# schematic_motor_driver_v3.net
KiCad netlist of a schematic drawn in Altium Designer
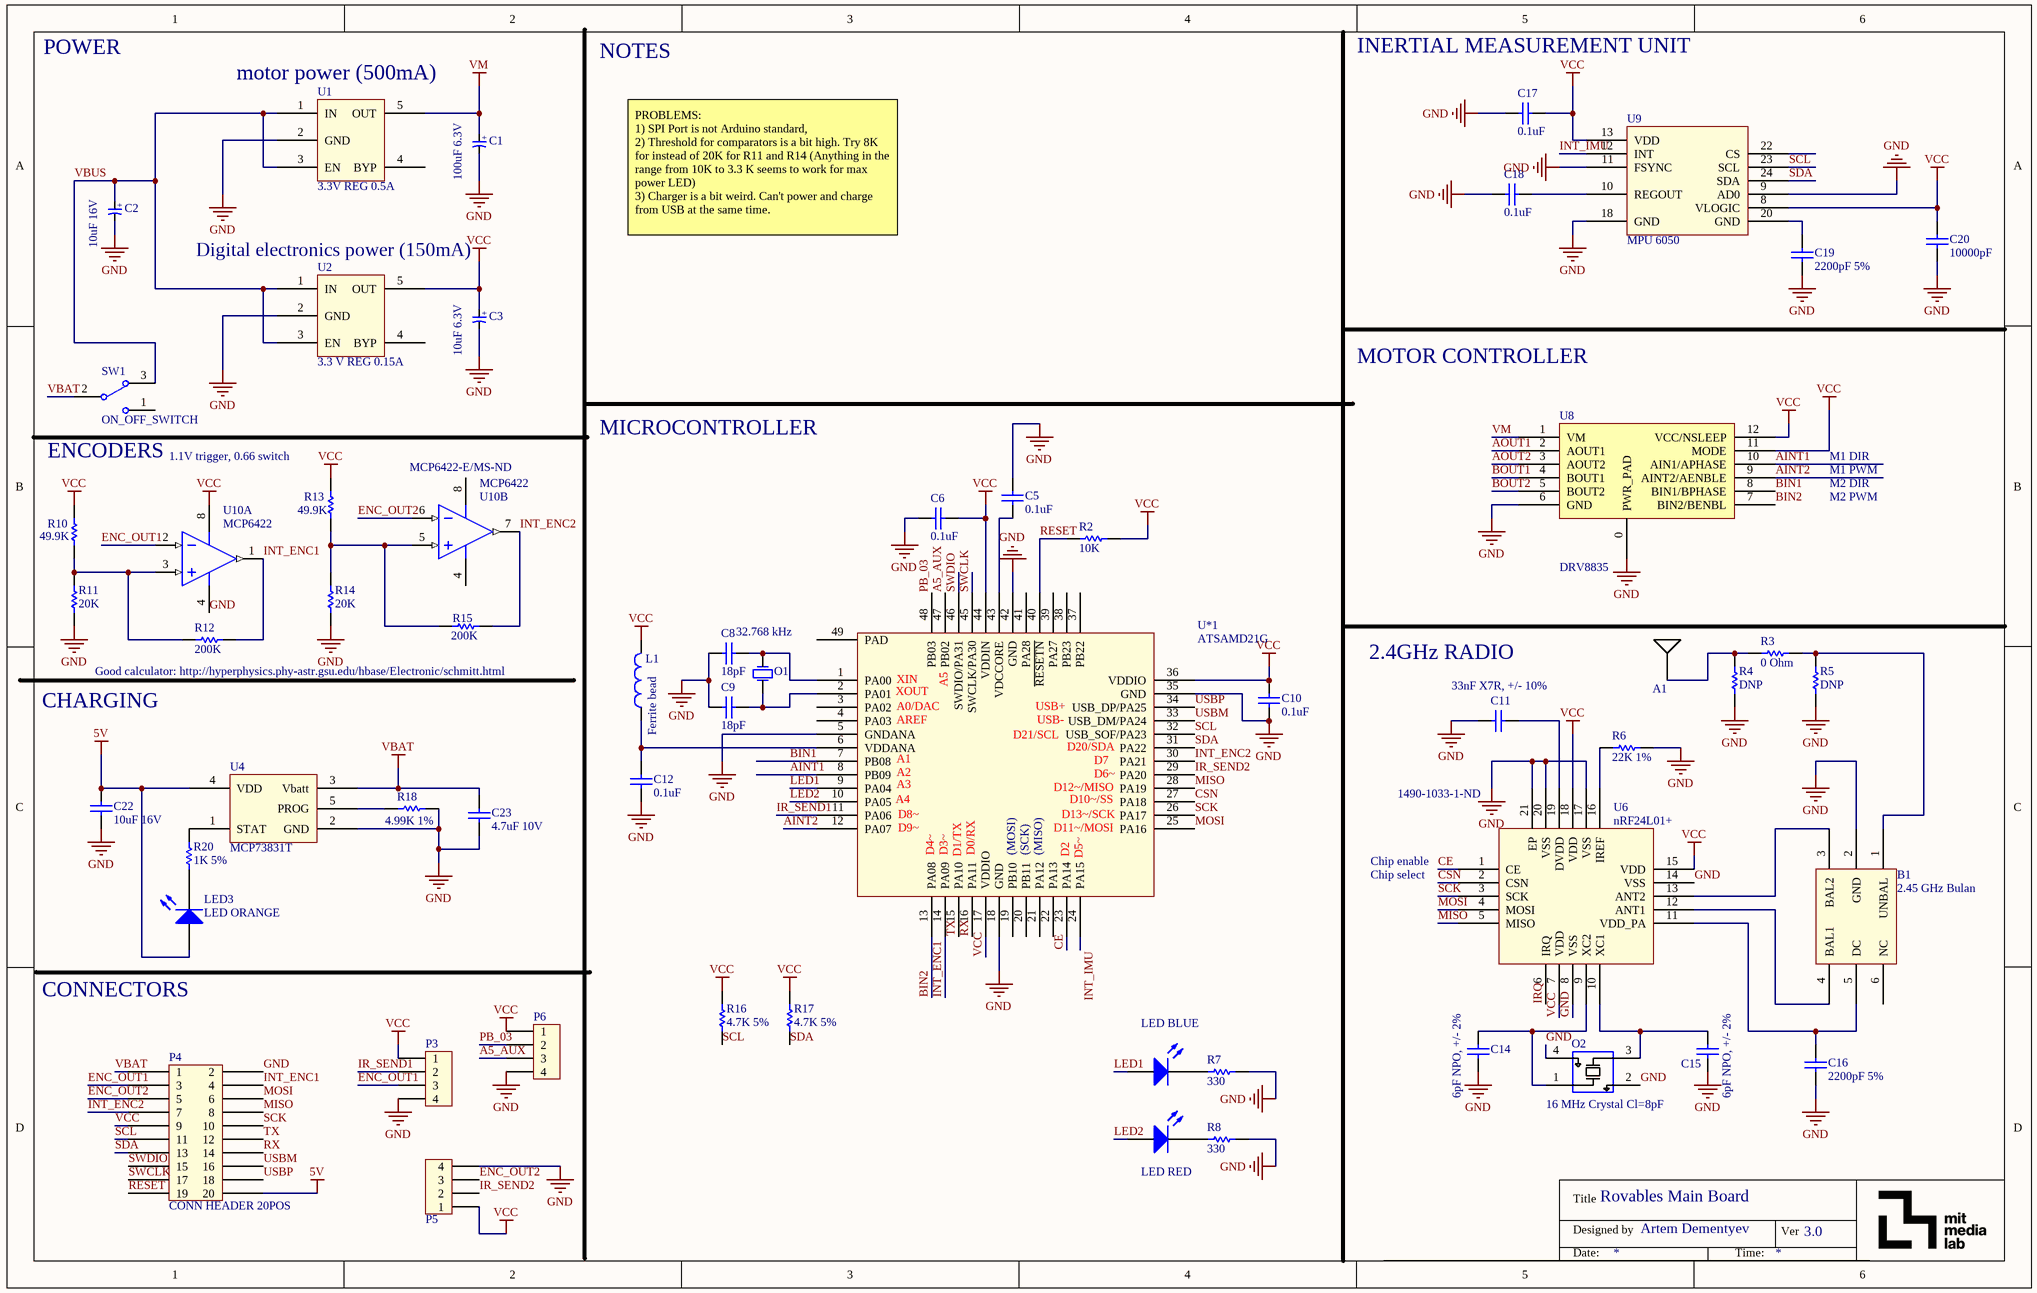
[diagram p0: schematic_motor_driver_v3.SchDoc]

(export (version "E")
  (design (tool "Eeschema 10.0.6"))
  (components
    (comp (ref "A1")
      (value "2.4GHz SMT On-ground MID Chip Antenna")
      (footprint "47948-0001")
      (description "Bluetooth antenna")
      (fields (field (name "DIGIKEY PART NUMBER") "WM4893CT-ND") (field (name "MANUFACTURER") "Molex"))
      (libsource (lib "Artem_Library") (part "2.4GHz SMT On-ground MID Chip Antenna"))
    )
    (comp (ref "B1")
      (value "2.45 GHz Bulan")
      (footprint "2450BM14A0002")
      (description "for nRF8001 chip")
      (libsource (lib "Artem_Library") (part "2.45 GHz Bulan"))
    )
    (comp (ref "C1")
      (value "100uF 6.3V")
      (footprint "CAP1206")
      (description "Polarised capacitor")
      (libsource (lib "PassiveSMT") (part "Capacitor_pol"))
    )
    (comp (ref "C2")
      (value "10uF 16V")
      (footprint "CAP0805")
      (description "Polarised capacitor")
      (fields (field (name "DIGIKEY PART NUMBER") "478-8654-1-ND"))
      (libsource (lib "PassiveSMT") (part "Capacitor_pol"))
    )
    (comp (ref "C3")
      (value "10uF 6.3V")
      (footprint "0805 TANTALUM")
      (description "Polarised capacitor")
      (fields (field (name "DIGIKEY PART NUMBER") "478-9265-1-ND"))
      (libsource (lib "PassiveSMT") (part "Capacitor_pol"))
    )
    (comp (ref "C5")
      (value "0.1uF")
      (footprint "0603W")
      (description "SMD Cap 1206")
      (libsource (lib "Artem_Library") (part "Capacitor"))
    )
    (comp (ref "C6")
      (value "0.1uF")
      (footprint "0402 CAPACITOR")
      (description "SMD Cap 1206")
      (libsource (lib "Artem_Library") (part "Capacitor"))
    )
    (comp (ref "C8")
      (value "18pF")
      (footprint "0402 CAPACITOR")
      (description "SMD Cap 1206")
      (libsource (lib "Artem_Library") (part "Capacitor"))
    )
    (comp (ref "C9")
      (value "18pF")
      (footprint "0402 CAPACITOR")
      (description "SMD Cap 1206")
      (libsource (lib "Artem_Library") (part "Capacitor"))
    )
    (comp (ref "C10")
      (value "0.1uF")
      (footprint "0402 CAPACITOR")
      (description "SMD Cap 1206")
      (libsource (lib "Artem_Library") (part "Capacitor"))
    )
    (comp (ref "C11")
      (value "33nF X7R, +/- 10%")
      (footprint "0402 CAPACITOR")
      (description "SMD Cap 1206")
      (libsource (lib "Artem_Library") (part "Capacitor"))
    )
    (comp (ref "C12")
      (value "0.1uF")
      (footprint "0603W")
      (description "SMD Cap 1206")
      (libsource (lib "Artem_Library") (part "Capacitor"))
    )
    (comp (ref "C14")
      (value "6pF NPO, +/- 2%")
      (footprint "0402 CAPACITOR")
      (description "SMD Cap 1206")
      (libsource (lib "Artem_Library") (part "Capacitor"))
    )
    (comp (ref "C15")
      (value "6pF NPO, +/- 2%")
      (footprint "0402 CAPACITOR")
      (description "SMD Cap 1206")
      (libsource (lib "Artem_Library") (part "Capacitor"))
    )
    (comp (ref "C16")
      (value "2200pF 5%")
      (footprint "0402 CAPACITOR")
      (description "SMD Cap 1206")
      (libsource (lib "Artem_Library") (part "Capacitor"))
    )
    (comp (ref "C17")
      (value "0.1uF")
      (footprint "0402 CAPACITOR")
      (description "SMD Cap 1206")
      (libsource (lib "Artem_Library") (part "Capacitor"))
    )
    (comp (ref "C18")
      (value "0.1uF")
      (footprint "0402 CAPACITOR")
      (description "SMD Cap 1206")
      (libsource (lib "Artem_Library") (part "Capacitor"))
    )
    (comp (ref "C19")
      (value "2200pF 5%")
      (footprint "0402 CAPACITOR")
      (description "SMD Cap 1206")
      (libsource (lib "Artem_Library") (part "Capacitor"))
    )
    (comp (ref "C20")
      (value "10000pF")
      (footprint "0402 CAPACITOR")
      (description "SMD Cap 1206")
      (libsource (lib "Artem_Library") (part "Capacitor"))
    )
    (comp (ref "C22")
      (value "10uF 16V")
      (footprint "0603W")
      (description "SMD Cap 1206")
      (libsource (lib "Artem_Library") (part "Capacitor"))
    )
    (comp (ref "C23")
      (value "4.7uF 10V")
      (footprint "0603W")
      (description "SMD Cap 1206")
      (libsource (lib "Artem_Library") (part "Capacitor"))
    )
    (comp (ref "L1")
      (value "Ferrite bead")
      (footprint "0603W")
      (libsource (lib "Artem_Library") (part "INDUCTOR Low DCR"))
    )
    (comp (ref "LED1")
      (value "LED BLUE")
      (footprint "0402W")
      (description "LED SMD 1206/0603")
      (libsource (lib "Artem_Library") (part "LED"))
    )
    (comp (ref "LED2")
      (value "LED RED")
      (footprint "0402W")
      (description "LED SMD 1206/0603")
      (libsource (lib "Artem_Library") (part "LED"))
    )
    (comp (ref "LED3")
      (value "LED ORANGE")
      (footprint "0402W")
      (description "LED SMD 1206/0603")
      (libsource (lib "Artem_Library") (part "LED"))
    )
    (comp (ref "O1")
      (value "32.768 kHz")
      (footprint "32.768 Crystal")
      (libsource (lib "Artem_Library") (part "32.768 Crystal"))
    )
    (comp (ref "O2")
      (value "16 MHz Crystal Cl=8pF")
      (footprint "2.5 x 2.0 crystal")
      (description "For BLE use")
      (libsource (lib "Artem_Library") (part "16 MHz Crystal Wireless"))
    )
    (comp (ref "P3")
      (value "FH33J-4S-0.5SH(99)")
      (footprint "FH33J-4S-0.5SH(99)")
      (description "0.5mm FPC connector")
      (fields (field (name "DIGIKEY PART NUMBER") "H124646CT-ND"))
      (libsource (lib "") (part "FH33J-4S-0.5SH(99)_1"))
    )
    (comp (ref "P4")
      (value "CONN HEADER 20POS")
      (footprint "DF12 20 POS")
      (fields
        (field (name "DIGIKEY PART NUMBER") "H11743CT-ND")
        (field (name "MANUFACTURER PART NUMBER") "DF12D(4.0)-20DP-0.5V(81)")
        (field (name "MANUFACTURER") "Hirose Electric Co Ltd")
      )
      (libsource (lib "Artem_Library") (part "CONN HEADER 20POS"))
    )
    (comp (ref "P5")
      (value "FH33J-4S-0.5SH(99)")
      (footprint "FH33J-4S-0.5SH(99)")
      (description "0.5mm FPC connector")
      (fields (field (name "DIGIKEY PART NUMBER") "H124646CT-ND"))
      (libsource (lib "Artem_Library") (part "FH33J-4S-0.5SH(99)"))
    )
    (comp (ref "P6")
      (value "FH33J-4S-0.5SH(99)")
      (footprint "FH33J-4S-0.5SH(99)")
      (description "0.5mm FPC connector")
      (fields (field (name "DIGIKEY PART NUMBER") "H124646CT-ND"))
      (libsource (lib "") (part "FH33J-4S-0.5SH(99)_1"))
    )
    (comp (ref "R2")
      (value "10K")
      (footprint "0402 RESISTOR")
      (libsource (lib "Artem_Library") (part "Resistor"))
    )
    (comp (ref "R3")
      (value "0 Ohm")
      (footprint "0402 RESISTOR")
      (libsource (lib "Artem_Library") (part "Resistor"))
    )
    (comp (ref "R4")
      (value "DNP")
      (footprint "0402 RESISTOR")
      (libsource (lib "Artem_Library") (part "Resistor"))
    )
    (comp (ref "R5")
      (value "DNP")
      (footprint "0402 RESISTOR")
      (libsource (lib "Artem_Library") (part "Resistor"))
    )
    (comp (ref "R6")
      (value "22K 1%")
      (footprint "0402 RESISTOR")
      (libsource (lib "Artem_Library") (part "Resistor"))
    )
    (comp (ref "R7")
      (value "330")
      (footprint "0402 RESISTOR")
      (libsource (lib "Artem_Library") (part "Resistor"))
    )
    (comp (ref "R8")
      (value "330")
      (footprint "0402 RESISTOR")
      (libsource (lib "Artem_Library") (part "Resistor"))
    )
    (comp (ref "R10") (value "49.9K") (footprint "0603W") (libsource (lib "Artem_Library") (part "Resistor")))
    (comp (ref "R11") (value "20K") (footprint "0603W") (libsource (lib "Artem_Library") (part "Resistor")))
    (comp (ref "R12") (value "200K") (footprint "0603W") (libsource (lib "Artem_Library") (part "Resistor")))
    (comp (ref "R13") (value "49.9K") (footprint "0603W") (libsource (lib "Artem_Library") (part "Resistor")))
    (comp (ref "R14") (value "20K") (footprint "0603W") (libsource (lib "Artem_Library") (part "Resistor")))
    (comp (ref "R15") (value "200K") (footprint "0603W") (libsource (lib "Artem_Library") (part "Resistor")))
    (comp (ref "R16")
      (value "4.7K 5%")
      (footprint "0402 RESISTOR")
      (libsource (lib "Artem_Library") (part "Resistor"))
    )
    (comp (ref "R17")
      (value "4.7K 5%")
      (footprint "0402 RESISTOR")
      (libsource (lib "Artem_Library") (part "Resistor"))
    )
    (comp (ref "R18")
      (value "4.99K 1%")
      (footprint "0603W")
      (libsource (lib "Artem_Library") (part "Resistor"))
    )
    (comp (ref "R20") (value "1K 5%") (footprint "0603W") (libsource (lib "Artem_Library") (part "Resistor")))
    (comp (ref "SW1")
      (value "ON_OFF_SWITCH")
      (footprint "SWTICH_SMD_SIDE")
      (description "SPDT SMD Side Switch")
      (libsource (lib "Artem_Library") (part "ON_OFF_SWITCH"))
    )
    (comp (ref "U*1")
      (value "ATSAMD21G")
      (footprint "TQFN48")
      (description "IC MCU 32BIT 256KB FLASH 48TQFP")
      (fields (field (name "DIGIKEY PART NUMBER") "ATSAMD21G18A-AUTCT-ND"))
      (libsource (lib "Artem_Library") (part "ATSAMD21G"))
    )
    (comp (ref "U1")
      (value "3.3V REG 0.5A")
      (footprint "SOT-23-5")
      (description "5V LDO SMD")
      (libsource (lib "Artem_Library") (part "MIC5205_VOLTAGE_REG"))
    )
    (comp (ref "U2")
      (value "3.3 V REG 0.15A")
      (footprint "SOT-23-5")
      (description "5V LDO SMD")
      (libsource (lib "Artem_Library") (part "MIC5205_VOLTAGE_REG"))
    )
    (comp (ref "U4")
      (value "MCP73831T")
      (footprint "SOT-23-5")
      (fields
        (field (name "DIGIKEY PART NUMBER") "MCP73831T-2ACI/OTTR-ND")
        (field (name "MANUFACTURER PART NUMBER") "MCP73831T-2ACI/OT")
        (field (name "MANUFACTURER") "Microchip")
      )
      (libsource (lib "Artem_Library") (part "MCP73831T"))
    )
    (comp (ref "U6")
      (value "nRF24L01+")
      (footprint "QFN20")
      (description "2.4 GHz Radio")
      (fields
        (field (name "DIGIKEY PART NUMBER") "1490-1033-1-ND")
        (field (name "MANUFACTURER PART NUMBER") "nRF24L01P-R")
        (field (name "SUPPLIER PART NUMBER 1") "1490-1033-1-ND")
      )
      (libsource (lib "Artem_Library") (part "nRF24L01+"))
    )
    (comp (ref "U8")
      (value "DRV8835")
      (footprint "WSON-16")
      (fields
        (field (name "DIGIKEY PART NUMBER") "296-30391-1-ND")
        (field (name "MANUFACTURER") "Texas Instruments")
        (field (name "MANUFACTURER PART NUMBER") "DRV8835DSSR")
      )
      (libsource (lib "Artem_Library") (part "DRV8835"))
    )
    (comp (ref "U9")
      (value "MPU 6050")
      (footprint "QFN24")
      (description "Gyro / accelerometer combo")
      (libsource (lib "Artem_Library") (part "MPU_6500"))
    )
    (comp (ref "U10")
      (value "MCP6422")
      (footprint "MSOP-MS8_N")
      (description "4.4 µA/Amplifier, 90 kHz Op Amp")
      (fields
        (field (name "DIGIKEY PART NUMBER") "MCP6422-E/MS-ND")
        (field (name "MANUFACTURER") "Microchip Technology")
        (field (name "SUPPLIER PART NUMBER 1") "MCP6422-E/MS-ND")
      )
      (libsource (lib "Artem_Library") (part "MCP6422"))
    )
  )
  (nets
    (net (code "1") (name "/A5_AUX") (class "Default")
      (node (ref "P6") (pin "3") (pinfunction "3_3") (pintype "passive"))
      (node (ref "U*1") (pin "47") (pinfunction "PB02_47") (pintype "passive"))
    )
    (net (code "2") (name "/AINT1") (class "Default")
      (node (ref "U*1") (pin "8") (pinfunction "PB09_8") (pintype "passive"))
      (node (ref "U8") (pin "10") (pinfunction "AIN1/APHASE_10") (pintype "passive"))
    )
    (net (code "3") (name "/AINT2") (class "Default")
      (node (ref "U*1") (pin "12") (pinfunction "PA07_12") (pintype "passive"))
      (node (ref "U8") (pin "9") (pinfunction "AINT2/AENBLE_9") (pintype "passive"))
    )
    (net (code "4") (name "/AOUT1") (class "Default")
      (node (ref "U8") (pin "2") (pinfunction "AOUT1_2") (pintype "passive"))
    )
    (net (code "5") (name "/AOUT2") (class "Default")
      (node (ref "U8") (pin "3") (pinfunction "AOUT2_3") (pintype "passive"))
    )
    (net (code "6") (name "/BIN1") (class "Default")
      (node (ref "U*1") (pin "7") (pinfunction "PB08_7") (pintype "passive"))
      (node (ref "U8") (pin "8") (pinfunction "BIN1/BPHASE_8") (pintype "passive"))
    )
    (net (code "7") (name "/BIN2") (class "Default")
      (node (ref "U*1") (pin "13") (pinfunction "PA08_13") (pintype "passive"))
      (node (ref "U8") (pin "7") (pinfunction "BIN2/BENBL_7") (pintype "passive"))
    )
    (net (code "8") (name "/BOUT1") (class "Default")
      (node (ref "U8") (pin "4") (pinfunction "BOUT1_4") (pintype "passive"))
    )
    (net (code "9") (name "/BOUT2") (class "Default")
      (node (ref "U8") (pin "5") (pinfunction "BOUT2_5") (pintype "passive"))
    )
    (net (code "10") (name "/CE") (class "Default")
      (node (ref "U*1") (pin "23") (pinfunction "PA14_23") (pintype "passive"))
      (node (ref "U6") (pin "1") (pinfunction "CE_1") (pintype "passive"))
    )
    (net (code "11") (name "/CSN") (class "Default")
      (node (ref "U*1") (pin "27") (pinfunction "PA18_27") (pintype "passive"))
      (node (ref "U6") (pin "2") (pinfunction "CSN_2") (pintype "passive"))
    )
    (net (code "12") (name "/ENC_OUT1") (class "Default")
      (node (ref "P3") (pin "3") (pinfunction "3_3") (pintype "passive"))
      (node (ref "P4") (pin "3") (pinfunction "3_3") (pintype "passive"))
      (node (ref "U10") (pin "2") (pinfunction "VINA-_2") (pintype "input"))
    )
    (net (code "13") (name "/ENC_OUT2") (class "Default")
      (node (ref "P4") (pin "5") (pinfunction "5_5") (pintype "passive"))
      (node (ref "P5") (pin "3") (pinfunction "3_3") (pintype "passive"))
      (node (ref "U10") (pin "6") (pinfunction "VINB-_6") (pintype "input"))
    )
    (net (code "14") (name "/INT_ENC1") (class "Default")
      (node (ref "P4") (pin "4") (pinfunction "4_4") (pintype "passive"))
      (node (ref "R12") (pin "1") (pinfunction "1_1") (pintype "passive"))
      (node (ref "U*1") (pin "14") (pinfunction "PA09_14") (pintype "passive"))
      (node (ref "U10") (pin "1") (pinfunction "VOUTA_1") (pintype "output"))
    )
    (net (code "15") (name "/INT_ENC2") (class "Default")
      (node (ref "P4") (pin "7") (pinfunction "7_7") (pintype "passive"))
      (node (ref "R15") (pin "1") (pinfunction "1_1") (pintype "passive"))
      (node (ref "U*1") (pin "30") (pinfunction "PA21_30") (pintype "passive"))
      (node (ref "U10") (pin "7") (pinfunction "VOUTB_7") (pintype "output"))
    )
    (net (code "16") (name "/INT_IMU") (class "Default")
      (node (ref "U*1") (pin "24") (pinfunction "PA15_24") (pintype "passive"))
      (node (ref "U9") (pin "12") (pinfunction "INT_12") (pintype "passive"))
    )
    (net (code "17") (name "/IRQ") (class "Default")
      (node (ref "U6") (pin "6") (pinfunction "IRQ_6") (pintype "passive"))
    )
    (net (code "18") (name "/IR_SEND1") (class "Default")
      (node (ref "P3") (pin "2") (pinfunction "2_2") (pintype "passive"))
      (node (ref "U*1") (pin "11") (pinfunction "PA06_11") (pintype "passive"))
    )
    (net (code "19") (name "/IR_SEND2") (class "Default")
      (node (ref "P5") (pin "2") (pinfunction "2_2") (pintype "passive"))
      (node (ref "U*1") (pin "29") (pinfunction "PA20_29") (pintype "passive"))
    )
    (net (code "20") (name "/LED1") (class "Default")
      (node (ref "LED1") (pin "1") (pinfunction "A_1") (pintype "passive"))
      (node (ref "U*1") (pin "9") (pinfunction "PA04_9") (pintype "passive"))
    )
    (net (code "21") (name "/LED2") (class "Default")
      (node (ref "LED2") (pin "1") (pinfunction "A_1") (pintype "passive"))
      (node (ref "U*1") (pin "10") (pinfunction "PA05_10") (pintype "passive"))
    )
    (net (code "22") (name "/MISO") (class "Default")
      (node (ref "P4") (pin "8") (pinfunction "8_8") (pintype "passive"))
      (node (ref "U*1") (pin "28") (pinfunction "PA19_28") (pintype "passive"))
      (node (ref "U6") (pin "5") (pinfunction "MISO_5") (pintype "passive"))
    )
    (net (code "23") (name "/MOSI") (class "Default")
      (node (ref "P4") (pin "6") (pinfunction "6_6") (pintype "passive"))
      (node (ref "U*1") (pin "25") (pinfunction "PA16_25") (pintype "passive"))
      (node (ref "U6") (pin "4") (pinfunction "MOSI_4") (pintype "passive"))
    )
    (net (code "24") (name "/PB_03") (class "Default")
      (node (ref "P6") (pin "2") (pinfunction "2_2") (pintype "passive"))
      (node (ref "U*1") (pin "48") (pinfunction "PB03_48") (pintype "passive"))
    )
    (net (code "25") (name "/RESET") (class "Default")
      (node (ref "P4") (pin "19") (pinfunction "19_19") (pintype "passive"))
      (node (ref "R2") (pin "2") (pinfunction "2_2") (pintype "passive"))
      (node (ref "U*1") (pin "40") (pinfunction "~{RESETN}_40") (pintype "passive"))
    )
    (net (code "26") (name "/RX") (class "Default")
      (node (ref "P4") (pin "14") (pinfunction "14_14") (pintype "passive"))
      (node (ref "U*1") (pin "16") (pinfunction "PA11_16") (pintype "passive"))
    )
    (net (code "27") (name "/SCK") (class "Default")
      (node (ref "P4") (pin "10") (pinfunction "10_10") (pintype "passive"))
      (node (ref "U*1") (pin "26") (pinfunction "PA17_26") (pintype "passive"))
      (node (ref "U6") (pin "3") (pinfunction "SCK_3") (pintype "passive"))
    )
    (net (code "28") (name "/SCL") (class "Default")
      (node (ref "P4") (pin "11") (pinfunction "11_11") (pintype "passive"))
      (node (ref "R16") (pin "2") (pinfunction "2_2") (pintype "passive"))
      (node (ref "U*1") (pin "32") (pinfunction "USB_SOF/PA23_32") (pintype "passive"))
      (node (ref "U9") (pin "23") (pinfunction "SCL_23") (pintype "passive"))
    )
    (net (code "29") (name "/SDA") (class "Default")
      (node (ref "P4") (pin "13") (pinfunction "13_13") (pintype "passive"))
      (node (ref "R17") (pin "2") (pinfunction "2_2") (pintype "passive"))
      (node (ref "U*1") (pin "31") (pinfunction "PA22_31") (pintype "passive"))
      (node (ref "U9") (pin "24") (pinfunction "SDA_24") (pintype "passive"))
    )
    (net (code "30") (name "/SWCLK") (class "Default")
      (node (ref "P4") (pin "17") (pinfunction "17_17") (pintype "passive"))
      (node (ref "U*1") (pin "45") (pinfunction "SWCLK/PA30_45") (pintype "passive"))
    )
    (net (code "31") (name "/SWDIO") (class "Default")
      (node (ref "P4") (pin "15") (pinfunction "15_15") (pintype "passive"))
      (node (ref "U*1") (pin "46") (pinfunction "SWDIO/PA31_46") (pintype "passive"))
    )
    (net (code "32") (name "/TX") (class "Default")
      (node (ref "P4") (pin "12") (pinfunction "12_12") (pintype "passive"))
      (node (ref "U*1") (pin "15") (pinfunction "PA10_15") (pintype "passive"))
    )
    (net (code "33") (name "/USBM") (class "Default")
      (node (ref "P4") (pin "16") (pinfunction "16_16") (pintype "passive"))
      (node (ref "U*1") (pin "33") (pinfunction "USB_DM/PA24_33") (pintype "passive"))
    )
    (net (code "34") (name "/USBP") (class "Default")
      (node (ref "P4") (pin "18") (pinfunction "18_18") (pintype "passive"))
      (node (ref "U*1") (pin "34") (pinfunction "USB_DP/PA25_34") (pintype "passive"))
    )
    (net (code "35") (name "/VBUS") (class "Default")
      (node (ref "C2") (pin "1") (pinfunction "1_1") (pintype "passive"))
      (node (ref "SW1") (pin "3") (pinfunction "3_3") (pintype "passive"))
      (node (ref "U1") (pin "1") (pinfunction "IN_1") (pintype "passive"))
      (node (ref "U1") (pin "3") (pinfunction "EN_3") (pintype "passive"))
      (node (ref "U2") (pin "1") (pinfunction "IN_1") (pintype "passive"))
      (node (ref "U2") (pin "3") (pinfunction "EN_3") (pintype "passive"))
    )
    (net (code "36") (name "5V") (class "Default")
      (node (ref "C22") (pin "1") (pinfunction "1_1") (pintype "passive"))
      (node (ref "LED3") (pin "1") (pinfunction "A_1") (pintype "passive"))
      (node (ref "P4") (pin "20") (pinfunction "20_20") (pintype "passive"))
      (node (ref "U4") (pin "4") (pinfunction "VDD_4") (pintype "passive"))
    )
    (net (code "37") (name "GND") (class "Default")
      (node (ref "B1") (pin "2") (pinfunction "GND_2") (pintype "passive"))
      (node (ref "C1") (pin "2") (pinfunction "2_2") (pintype "passive"))
      (node (ref "C10") (pin "1") (pinfunction "1_1") (pintype "passive"))
      (node (ref "C11") (pin "2") (pinfunction "2_2") (pintype "passive"))
      (node (ref "C12") (pin "1") (pinfunction "1_1") (pintype "passive"))
      (node (ref "C14") (pin "1") (pinfunction "1_1") (pintype "passive"))
      (node (ref "C15") (pin "1") (pinfunction "1_1") (pintype "passive"))
      (node (ref "C16") (pin "1") (pinfunction "1_1") (pintype "passive"))
      (node (ref "C17") (pin "2") (pinfunction "2_2") (pintype "passive"))
      (node (ref "C18") (pin "2") (pinfunction "2_2") (pintype "passive"))
      (node (ref "C19") (pin "2") (pinfunction "2_2") (pintype "passive"))
      (node (ref "C2") (pin "2") (pinfunction "2_2") (pintype "passive"))
      (node (ref "C20") (pin "2") (pinfunction "2_2") (pintype "passive"))
      (node (ref "C22") (pin "2") (pinfunction "2_2") (pintype "passive"))
      (node (ref "C23") (pin "2") (pinfunction "2_2") (pintype "passive"))
      (node (ref "C3") (pin "2") (pinfunction "2_2") (pintype "passive"))
      (node (ref "C5") (pin "2") (pinfunction "2_2") (pintype "passive"))
      (node (ref "C6") (pin "2") (pinfunction "2_2") (pintype "passive"))
      (node (ref "C8") (pin "2") (pinfunction "2_2") (pintype "passive"))
      (node (ref "C9") (pin "2") (pinfunction "2_2") (pintype "passive"))
      (node (ref "O2") (pin "2") (pinfunction "Gnd_2") (pintype "passive"))
      (node (ref "O2") (pin "4") (pinfunction "Gnd_4") (pintype "passive"))
      (node (ref "P3") (pin "4") (pinfunction "4_4") (pintype "passive"))
      (node (ref "P4") (pin "2") (pinfunction "2_2") (pintype "passive"))
      (node (ref "P5") (pin "4") (pinfunction "4_4") (pintype "passive"))
      (node (ref "P6") (pin "4") (pinfunction "4_4") (pintype "passive"))
      (node (ref "R11") (pin "1") (pinfunction "1_1") (pintype "passive"))
      (node (ref "R14") (pin "1") (pinfunction "1_1") (pintype "passive"))
      (node (ref "R18") (pin "1") (pinfunction "1_1") (pintype "passive"))
      (node (ref "R4") (pin "1") (pinfunction "1_1") (pintype "passive"))
      (node (ref "R5") (pin "1") (pinfunction "1_1") (pintype "passive"))
      (node (ref "R6") (pin "1") (pinfunction "1_1") (pintype "passive"))
      (node (ref "R7") (pin "1") (pinfunction "1_1") (pintype "passive"))
      (node (ref "R8") (pin "1") (pinfunction "1_1") (pintype "passive"))
      (node (ref "U*1") (pin "18") (pinfunction "GND_18") (pintype "passive"))
      (node (ref "U*1") (pin "35") (pinfunction "GND_35") (pintype "passive"))
      (node (ref "U*1") (pin "42") (pinfunction "GND_42") (pintype "passive"))
      (node (ref "U*1") (pin "5") (pinfunction "GNDANA_5") (pintype "passive"))
      (node (ref "U1") (pin "2") (pinfunction "GND_2") (pintype "passive"))
      (node (ref "U10") (pin "4") (pinfunction "VSS_4") (pintype "power_in"))
      (node (ref "U2") (pin "2") (pinfunction "GND_2") (pintype "passive"))
      (node (ref "U4") (pin "2") (pinfunction "GND_2") (pintype "passive"))
      (node (ref "U6") (pin "14") (pinfunction "VSS_14") (pintype "passive"))
      (node (ref "U6") (pin "17") (pinfunction "VSS_17") (pintype "passive"))
      (node (ref "U6") (pin "20") (pinfunction "VSS_20") (pintype "passive"))
      (node (ref "U6") (pin "21") (pinfunction "EP_21") (pintype "passive"))
      (node (ref "U6") (pin "8") (pinfunction "VSS_8") (pintype "passive"))
      (node (ref "U8") (pin "0") (pinfunction "PWR_PAD_0") (pintype "passive"))
      (node (ref "U8") (pin "6") (pinfunction "GND_6") (pintype "passive"))
      (node (ref "U9") (pin "11") (pinfunction "FSYNC_11") (pintype "passive"))
      (node (ref "U9") (pin "18") (pinfunction "GND_18") (pintype "passive"))
      (node (ref "U9") (pin "9") (pinfunction "AD0_9") (pintype "passive"))
    )
    (net (code "38") (name "Net-(A1-Pad1)") (class "Default")
      (node (ref "A1") (pin "1") (pinfunction "1_1") (pintype "passive"))
      (node (ref "R3") (pin "1") (pinfunction "1_1") (pintype "passive"))
      (node (ref "R4") (pin "2") (pinfunction "2_2") (pintype "passive"))
    )
    (net (code "39") (name "Net-(B1-BAL1)") (class "Default")
      (node (ref "B1") (pin "4") (pinfunction "BAL1_4") (pintype "passive"))
      (node (ref "U6") (pin "12") (pinfunction "ANT1_12") (pintype "passive"))
    )
    (net (code "40") (name "Net-(B1-BAL2)") (class "Default")
      (node (ref "B1") (pin "3") (pinfunction "BAL2_3") (pintype "passive"))
      (node (ref "U6") (pin "13") (pinfunction "ANT2_13") (pintype "passive"))
    )
    (net (code "41") (name "Net-(B1-DC)") (class "Default")
      (node (ref "B1") (pin "5") (pinfunction "DC_5") (pintype "passive"))
      (node (ref "C16") (pin "2") (pinfunction "2_2") (pintype "passive"))
      (node (ref "U6") (pin "11") (pinfunction "VDD_PA_11") (pintype "passive"))
    )
    (net (code "42") (name "Net-(B1-UNBAL)") (class "Default")
      (node (ref "B1") (pin "1") (pinfunction "UNBAL_1") (pintype "passive"))
      (node (ref "R3") (pin "2") (pinfunction "2_2") (pintype "passive"))
      (node (ref "R5") (pin "2") (pinfunction "2_2") (pintype "passive"))
    )
    (net (code "43") (name "Net-(C19-Pad1)") (class "Default")
      (node (ref "C19") (pin "1") (pinfunction "1_1") (pintype "passive"))
      (node (ref "U9") (pin "20") (pinfunction "GND_20") (pintype "passive"))
    )
    (net (code "44") (name "Net-(LED1-K)") (class "Default")
      (node (ref "LED1") (pin "2") (pinfunction "K_2") (pintype "passive"))
      (node (ref "R7") (pin "2") (pinfunction "2_2") (pintype "passive"))
    )
    (net (code "45") (name "Net-(LED2-K)") (class "Default")
      (node (ref "LED2") (pin "2") (pinfunction "K_2") (pintype "passive"))
      (node (ref "R8") (pin "2") (pinfunction "2_2") (pintype "passive"))
    )
    (net (code "46") (name "Net-(LED3-K)") (class "Default")
      (node (ref "LED3") (pin "2") (pinfunction "K_2") (pintype "passive"))
      (node (ref "R20") (pin "1") (pinfunction "1_1") (pintype "passive"))
    )
    (net (code "47") (name "Net-(O2-XIN)") (class "Default")
      (node (ref "C14") (pin "2") (pinfunction "2_2") (pintype "passive"))
      (node (ref "O2") (pin "1") (pinfunction "XIN_1") (pintype "passive"))
      (node (ref "U6") (pin "9") (pinfunction "XC2_9") (pintype "passive"))
    )
    (net (code "48") (name "Net-(O2-XOUT)") (class "Default")
      (node (ref "C15") (pin "2") (pinfunction "2_2") (pintype "passive"))
      (node (ref "O2") (pin "3") (pinfunction "XOUT_3") (pintype "passive"))
      (node (ref "U6") (pin "10") (pinfunction "XC1_10") (pintype "passive"))
    )
    (net (code "49") (name "Net-(U*1-PA00)") (class "Default")
      (node (ref "C8") (pin "1") (pinfunction "1_1") (pintype "passive"))
      (node (ref "O1") (pin "1") (pinfunction "1_1") (pintype "passive"))
      (node (ref "U*1") (pin "1") (pinfunction "PA00_1") (pintype "passive"))
    )
    (net (code "50") (name "Net-(U*1-PA01)") (class "Default")
      (node (ref "C9") (pin "1") (pinfunction "1_1") (pintype "passive"))
      (node (ref "O1") (pin "2") (pinfunction "2_2") (pintype "passive"))
      (node (ref "U*1") (pin "2") (pinfunction "PA01_2") (pintype "passive"))
    )
    (net (code "51") (name "Net-(U*1-VDCCORE)") (class "Default")
      (node (ref "C5") (pin "1") (pinfunction "1_1") (pintype "passive"))
      (node (ref "U*1") (pin "43") (pinfunction "VDCCORE_43") (pintype "passive"))
    )
    (net (code "52") (name "Net-(U*1-VDDANA)") (class "Default")
      (node (ref "C12") (pin "2") (pinfunction "2_2") (pintype "passive"))
      (node (ref "L1") (pin "1") (pinfunction "1_1") (pintype "passive"))
      (node (ref "U*1") (pin "6") (pinfunction "VDDANA_6") (pintype "passive"))
    )
    (net (code "53") (name "Net-(U4-PROG)") (class "Default")
      (node (ref "R18") (pin "2") (pinfunction "2_2") (pintype "passive"))
      (node (ref "U4") (pin "5") (pinfunction "PROG_5") (pintype "passive"))
    )
    (net (code "54") (name "Net-(U4-STAT)") (class "Default")
      (node (ref "R20") (pin "2") (pinfunction "2_2") (pintype "passive"))
      (node (ref "U4") (pin "1") (pinfunction "STAT_1") (pintype "passive"))
    )
    (net (code "55") (name "Net-(U6-DVDD)") (class "Default")
      (node (ref "C11") (pin "1") (pinfunction "1_1") (pintype "passive"))
      (node (ref "U6") (pin "19") (pinfunction "DVDD_19") (pintype "passive"))
    )
    (net (code "56") (name "Net-(U6-IREF)") (class "Default")
      (node (ref "R6") (pin "2") (pinfunction "2_2") (pintype "passive"))
      (node (ref "U6") (pin "16") (pinfunction "IREF_16") (pintype "passive"))
    )
    (net (code "57") (name "Net-(U9-REGOUT)") (class "Default")
      (node (ref "C18") (pin "1") (pinfunction "1_1") (pintype "passive"))
      (node (ref "U9") (pin "10") (pinfunction "REGOUT_10") (pintype "passive"))
    )
    (net (code "58") (name "Net-(U10A-VINA+)") (class "Default")
      (node (ref "R10") (pin "1") (pinfunction "1_1") (pintype "passive"))
      (node (ref "R11") (pin "2") (pinfunction "2_2") (pintype "passive"))
      (node (ref "R12") (pin "2") (pinfunction "2_2") (pintype "passive"))
      (node (ref "U10") (pin "3") (pinfunction "VINA+_3") (pintype "input"))
    )
    (net (code "59") (name "Net-(U10B-VINB+)") (class "Default")
      (node (ref "R13") (pin "1") (pinfunction "1_1") (pintype "passive"))
      (node (ref "R14") (pin "2") (pinfunction "2_2") (pintype "passive"))
      (node (ref "R15") (pin "2") (pinfunction "2_2") (pintype "passive"))
      (node (ref "U10") (pin "5") (pinfunction "VINB+_5") (pintype "input"))
    )
    (net (code "60") (name "VBAT") (class "Default")
      (node (ref "C23") (pin "1") (pinfunction "1_1") (pintype "passive"))
      (node (ref "P4") (pin "1") (pinfunction "1_1") (pintype "passive"))
      (node (ref "SW1") (pin "2") (pinfunction "2_2") (pintype "passive"))
      (node (ref "U4") (pin "3") (pinfunction "Vbatt_3") (pintype "passive"))
    )
    (net (code "61") (name "VCC") (class "Default")
      (node (ref "C10") (pin "2") (pinfunction "2_2") (pintype "passive"))
      (node (ref "C17") (pin "1") (pinfunction "1_1") (pintype "passive"))
      (node (ref "C20") (pin "1") (pinfunction "1_1") (pintype "passive"))
      (node (ref "C3") (pin "1") (pinfunction "1_1") (pintype "passive"))
      (node (ref "C6") (pin "1") (pinfunction "1_1") (pintype "passive"))
      (node (ref "L1") (pin "2") (pinfunction "2_2") (pintype "passive"))
      (node (ref "P3") (pin "1") (pinfunction "1_1") (pintype "passive"))
      (node (ref "P4") (pin "9") (pinfunction "9_9") (pintype "passive"))
      (node (ref "P5") (pin "1") (pinfunction "1_1") (pintype "passive"))
      (node (ref "P6") (pin "1") (pinfunction "1_1") (pintype "passive"))
      (node (ref "R10") (pin "2") (pinfunction "2_2") (pintype "passive"))
      (node (ref "R13") (pin "2") (pinfunction "2_2") (pintype "passive"))
      (node (ref "R16") (pin "1") (pinfunction "1_1") (pintype "passive"))
      (node (ref "R17") (pin "1") (pinfunction "1_1") (pintype "passive"))
      (node (ref "R2") (pin "1") (pinfunction "1_1") (pintype "passive"))
      (node (ref "U*1") (pin "17") (pinfunction "VDDIO_17") (pintype "passive"))
      (node (ref "U*1") (pin "36") (pinfunction "VDDIO_36") (pintype "passive"))
      (node (ref "U*1") (pin "44") (pinfunction "VDDIN_44") (pintype "passive"))
      (node (ref "U10") (pin "8") (pinfunction "VDD_8") (pintype "power_in"))
      (node (ref "U2") (pin "5") (pinfunction "OUT_5") (pintype "passive"))
      (node (ref "U6") (pin "15") (pinfunction "VDD_15") (pintype "passive"))
      (node (ref "U6") (pin "18") (pinfunction "VDD_18") (pintype "passive"))
      (node (ref "U6") (pin "7") (pinfunction "VDD_7") (pintype "passive"))
      (node (ref "U8") (pin "11") (pinfunction "MODE_11") (pintype "passive"))
      (node (ref "U8") (pin "12") (pinfunction "VCC/NSLEEP_12") (pintype "passive"))
      (node (ref "U9") (pin "13") (pinfunction "VDD_13") (pintype "passive"))
      (node (ref "U9") (pin "8") (pinfunction "VLOGIC_8") (pintype "passive"))
    )
    (net (code "62") (name "VM") (class "Default")
      (node (ref "C1") (pin "1") (pinfunction "1_1") (pintype "passive"))
      (node (ref "U1") (pin "5") (pinfunction "OUT_5") (pintype "passive"))
      (node (ref "U8") (pin "1") (pinfunction "VM_1") (pintype "passive"))
    )
    (net (code "63") (name "unconnected-(B1-NC-Pad6)") (class "Default")
      (node (ref "B1") (pin "6") (pinfunction "NC_6") (pintype "passive"))
    )
    (net (code "64") (name "unconnected-(SW1-Pad1)") (class "Default")
      (node (ref "SW1") (pin "1") (pinfunction "1_1") (pintype "passive"))
    )
    (net (code "65") (name "unconnected-(U*1-PA02-Pad3)") (class "Default")
      (node (ref "U*1") (pin "3") (pinfunction "PA02_3") (pintype "passive"))
    )
    (net (code "66") (name "unconnected-(U*1-PA03-Pad4)") (class "Default")
      (node (ref "U*1") (pin "4") (pinfunction "PA03_4") (pintype "passive"))
    )
    (net (code "67") (name "unconnected-(U*1-PA12-Pad21)") (class "Default")
      (node (ref "U*1") (pin "21") (pinfunction "PA12_21") (pintype "passive"))
    )
    (net (code "68") (name "unconnected-(U*1-PA13-Pad22)") (class "Default")
      (node (ref "U*1") (pin "22") (pinfunction "PA13_22") (pintype "passive"))
    )
    (net (code "69") (name "unconnected-(U*1-PA27-Pad39)") (class "Default")
      (node (ref "U*1") (pin "39") (pinfunction "PA27_39") (pintype "passive"))
    )
    (net (code "70") (name "unconnected-(U*1-PA28-Pad41)") (class "Default")
      (node (ref "U*1") (pin "41") (pinfunction "PA28_41") (pintype "passive"))
    )
    (net (code "71") (name "unconnected-(U*1-PAD-Pad49)") (class "Default")
      (node (ref "U*1") (pin "49") (pinfunction "PAD_49") (pintype "passive"))
    )
    (net (code "72") (name "unconnected-(U*1-PB10-Pad19)") (class "Default")
      (node (ref "U*1") (pin "19") (pinfunction "PB10_19") (pintype "passive"))
    )
    (net (code "73") (name "unconnected-(U*1-PB11-Pad20)") (class "Default")
      (node (ref "U*1") (pin "20") (pinfunction "PB11_20") (pintype "passive"))
    )
    (net (code "74") (name "unconnected-(U*1-PB22-Pad37)") (class "Default")
      (node (ref "U*1") (pin "37") (pinfunction "PB22_37") (pintype "passive"))
    )
    (net (code "75") (name "unconnected-(U*1-PB23-Pad38)") (class "Default")
      (node (ref "U*1") (pin "38") (pinfunction "PB23_38") (pintype "passive"))
    )
    (net (code "76") (name "unconnected-(U1-BYP-Pad4)") (class "Default")
      (node (ref "U1") (pin "4") (pinfunction "BYP_4") (pintype "passive"))
    )
    (net (code "77") (name "unconnected-(U2-BYP-Pad4)") (class "Default")
      (node (ref "U2") (pin "4") (pinfunction "BYP_4") (pintype "passive"))
    )
    (net (code "78") (name "unconnected-(U9-CS-Pad22)") (class "Default")
      (node (ref "U9") (pin "22") (pinfunction "CS_22") (pintype "passive"))
    )
    (net (code "79") (name "unconnected-(U10B-VDD-Pad8)") (class "Default")
      (node (ref "U10") (pin "8") (pinfunction "VDD_8") (pintype "power_in"))
    )
    (net (code "80") (name "unconnected-(U10B-VSS-Pad4)") (class "Default")
      (node (ref "U10") (pin "4") (pinfunction "VSS_4") (pintype "power_in"))
    )
  )
)
